# WienOscilator.net
KiCad netlist of a schematic drawn in Altium Designer
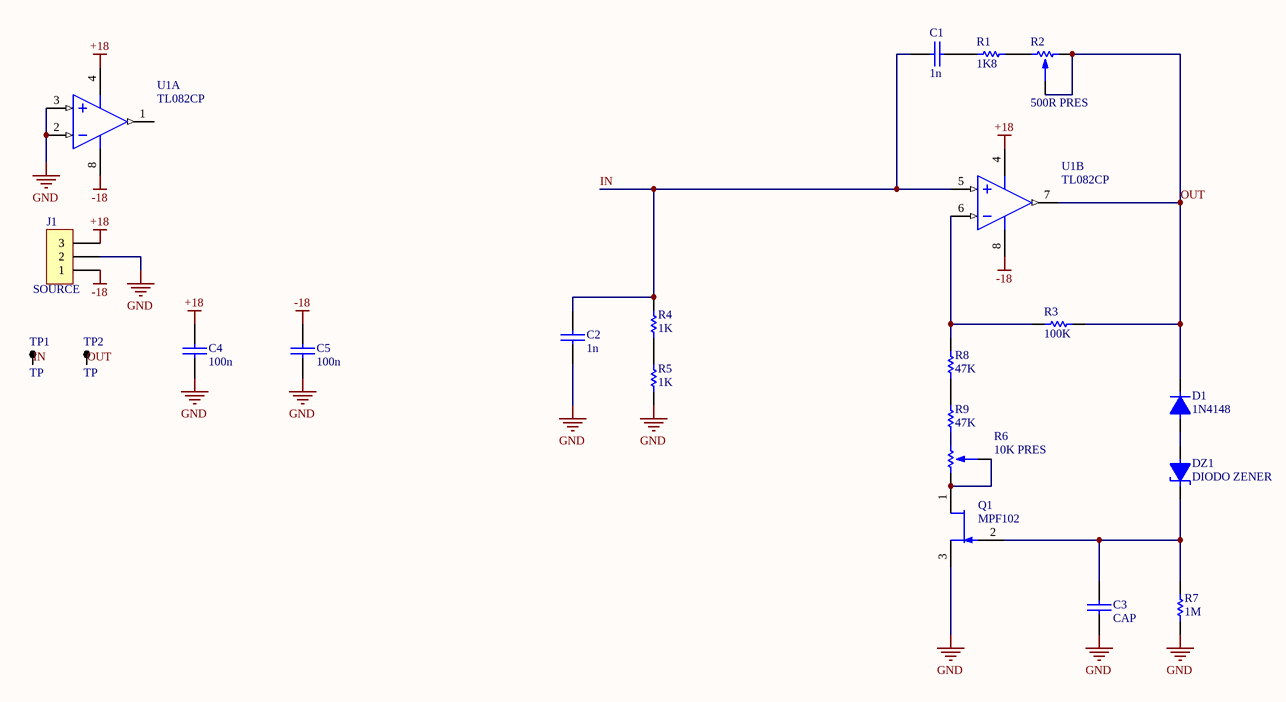
[diagram p0: WienOscilator.SchDoc]

(export (version "E")
  (design (tool "Eeschema 10.0.6"))
  (components
    (comp (ref "C1") (value "1n") (footprint "CAP200") (libsource (lib "LIBEBAL") (part "CAP")))
    (comp (ref "C2") (value "1n") (footprint "CAP200") (libsource (lib "LIBEBAL") (part "CAP")))
    (comp (ref "C3") (value "CAP") (footprint "CAP200") (libsource (lib "LIBEBAL") (part "CAP")))
    (comp (ref "C4") (value "100n") (footprint "CAP100") (libsource (lib "LIBEBAL") (part "CAP")))
    (comp (ref "C5") (value "100n") (footprint "CAP100") (libsource (lib "LIBEBAL") (part "CAP")))
    (comp (ref "D1") (value "1N4148") (footprint "DO41") (libsource (lib "LIBEBAL") (part "DIODO")))
    (comp (ref "DZ1")
      (value "DIODO ZENER")
      (footprint "DO41")
      (libsource (lib "LIB PIO IX") (part "DIODO ZENER"))
    )
    (comp (ref "J1")
      (value "SOURCE")
      (footprint "BORNERA3")
      (libsource (lib "LIB PIO IX") (part "BORNERA 3"))
    )
    (comp (ref "Q1")
      (value "MPF102")
      (footprint "TO92")
      (description "N-Channel JFET")
      (fields (field (name "PUBLISHER") "Altium Limited"))
      (libsource (lib "Miscellaneous Devices") (part "JFET-N"))
    )
    (comp (ref "R1") (value "1K8") (footprint "0805") (libsource (lib "LIBEBAL") (part "RES")))
    (comp (ref "R2")
      (value "500R PRES")
      (footprint "PRESET V")
      (libsource (lib "LIB PIO IX") (part "PRESET"))
    )
    (comp (ref "R3") (value "100K") (footprint "0805") (libsource (lib "LIBEBAL") (part "RES")))
    (comp (ref "R4") (value "1K") (footprint "0805") (libsource (lib "LIBEBAL") (part "RES")))
    (comp (ref "R5") (value "1K") (footprint "0805") (libsource (lib "LIBEBAL") (part "RES")))
    (comp (ref "R6") (value "10K PRES") (footprint "PRESET V") (libsource (lib "LIB PIO IX") (part "PRESET")))
    (comp (ref "R7") (value "1M") (footprint "0805") (libsource (lib "LIBEBAL") (part "RES")))
    (comp (ref "R8") (value "47K") (footprint "0805") (libsource (lib "LIBEBAL") (part "RES")))
    (comp (ref "R9") (value "47K") (footprint "0805") (libsource (lib "LIBEBAL") (part "RES")))
    (comp (ref "TP1") (value "TP") (footprint "TPTH") (libsource (lib "LIB PIO IX") (part "TP")))
    (comp (ref "TP2") (value "TP") (footprint "TPTH") (libsource (lib "LIB PIO IX") (part "TP")))
    (comp (ref "U1")
      (value "TL082CP")
      (footprint "N08E")
      (description "Wide Bandwidth Dual JFET Input Operational Amplifier, 8-pin MDIP")
      (fields
        (field (name "MANUFACTURER") "National Semiconductor")
        (field (name "PUBLISHER") "Altium Limited")
      )
      (libsource (lib "NSC Amplifier") (part "TL082CP"))
    )
  )
  (nets
    (net (code "1") (name "+18") (class "Default")
      (node (ref "C4") (pin "1") (pinfunction "1_1") (pintype "passive"))
      (node (ref "J1") (pin "3") (pinfunction "3_3") (pintype "passive"))
      (node (ref "U1") (pin "4") (pinfunction "V-_4") (pintype "power_in"))
    )
    (net (code "2") (name "-18") (class "Default")
      (node (ref "C5") (pin "1") (pinfunction "1_1") (pintype "passive"))
      (node (ref "J1") (pin "1") (pinfunction "1_1") (pintype "passive"))
      (node (ref "U1") (pin "8") (pinfunction "V+_8") (pintype "power_in"))
    )
    (net (code "3") (name "/IN") (class "Default")
      (node (ref "C1") (pin "1") (pinfunction "1_1") (pintype "passive"))
      (node (ref "C2") (pin "2") (pinfunction "2_2") (pintype "passive"))
      (node (ref "R4") (pin "1") (pinfunction "1_1") (pintype "passive"))
      (node (ref "TP1") (pin "1") (pinfunction "1_1") (pintype "passive"))
      (node (ref "U1") (pin "5") (pinfunction "INB+_5") (pintype "input"))
    )
    (net (code "4") (name "/OUT") (class "Default")
      (node (ref "D1") (pin "2") (pinfunction "2_2") (pintype "passive"))
      (node (ref "R2") (pin "1") (pinfunction "1_1") (pintype "passive"))
      (node (ref "R2") (pin "2") (pinfunction "2_2") (pintype "passive"))
      (node (ref "R3") (pin "1") (pinfunction "1_1") (pintype "passive"))
      (node (ref "TP2") (pin "1") (pinfunction "1_1") (pintype "passive"))
      (node (ref "U1") (pin "7") (pinfunction "OUTB_7") (pintype "output"))
    )
    (net (code "5") (name "GND") (class "Default")
      (node (ref "C2") (pin "1") (pinfunction "1_1") (pintype "passive"))
      (node (ref "C3") (pin "2") (pinfunction "2_2") (pintype "passive"))
      (node (ref "C4") (pin "2") (pinfunction "2_2") (pintype "passive"))
      (node (ref "C5") (pin "2") (pinfunction "2_2") (pintype "passive"))
      (node (ref "J1") (pin "2") (pinfunction "2_2") (pintype "passive"))
      (node (ref "Q1") (pin "3") (pinfunction "S_3") (pintype "passive"))
      (node (ref "R5") (pin "2") (pinfunction "2_2") (pintype "passive"))
      (node (ref "R7") (pin "1") (pinfunction "1_1") (pintype "passive"))
      (node (ref "U1") (pin "2") (pinfunction "INA-_2") (pintype "input"))
      (node (ref "U1") (pin "3") (pinfunction "INA+_3") (pintype "input"))
    )
    (net (code "6") (name "Net-(C1-Pad2)") (class "Default")
      (node (ref "C1") (pin "2") (pinfunction "2_2") (pintype "passive"))
      (node (ref "R1") (pin "2") (pinfunction "2_2") (pintype "passive"))
    )
    (net (code "7") (name "Net-(D1-Pad1)") (class "Default")
      (node (ref "D1") (pin "1") (pinfunction "1_1") (pintype "passive"))
      (node (ref "DZ1") (pin "1") (pinfunction "1_1") (pintype "passive"))
    )
    (net (code "8") (name "Net-(Q1-D)") (class "Default")
      (node (ref "Q1") (pin "1") (pinfunction "D_1") (pintype "passive"))
      (node (ref "R6") (pin "2") (pinfunction "2_2") (pintype "passive"))
      (node (ref "R6") (pin "3") (pinfunction "3_3") (pintype "passive"))
    )
    (net (code "9") (name "Net-(Q1-G)") (class "Default")
      (node (ref "C3") (pin "1") (pinfunction "1_1") (pintype "passive"))
      (node (ref "DZ1") (pin "2") (pinfunction "2_2") (pintype "passive"))
      (node (ref "Q1") (pin "2") (pinfunction "G_2") (pintype "passive"))
      (node (ref "R7") (pin "2") (pinfunction "2_2") (pintype "passive"))
    )
    (net (code "10") (name "Net-(R1-Pad1)") (class "Default")
      (node (ref "R1") (pin "1") (pinfunction "1_1") (pintype "passive"))
      (node (ref "R2") (pin "3") (pinfunction "3_3") (pintype "passive"))
    )
    (net (code "11") (name "Net-(R4-Pad2)") (class "Default")
      (node (ref "R4") (pin "2") (pinfunction "2_2") (pintype "passive"))
      (node (ref "R5") (pin "1") (pinfunction "1_1") (pintype "passive"))
    )
    (net (code "12") (name "Net-(R6-Pad1)") (class "Default")
      (node (ref "R6") (pin "1") (pinfunction "1_1") (pintype "passive"))
      (node (ref "R9") (pin "1") (pinfunction "1_1") (pintype "passive"))
    )
    (net (code "13") (name "Net-(R8-Pad1)") (class "Default")
      (node (ref "R8") (pin "1") (pinfunction "1_1") (pintype "passive"))
      (node (ref "R9") (pin "2") (pinfunction "2_2") (pintype "passive"))
    )
    (net (code "14") (name "Net-(U1B-INB-)") (class "Default")
      (node (ref "R3") (pin "2") (pinfunction "2_2") (pintype "passive"))
      (node (ref "R8") (pin "2") (pinfunction "2_2") (pintype "passive"))
      (node (ref "U1") (pin "6") (pinfunction "INB-_6") (pintype "input"))
    )
    (net (code "15") (name "unconnected-(U1A-OUTA-Pad1)") (class "Default")
      (node (ref "U1") (pin "1") (pinfunction "OUTA_1") (pintype "output"))
    )
  )
)
